# dp_tape_cutting_robot-logic.net
KiCad netlist of a schematic drawn in EAGLE
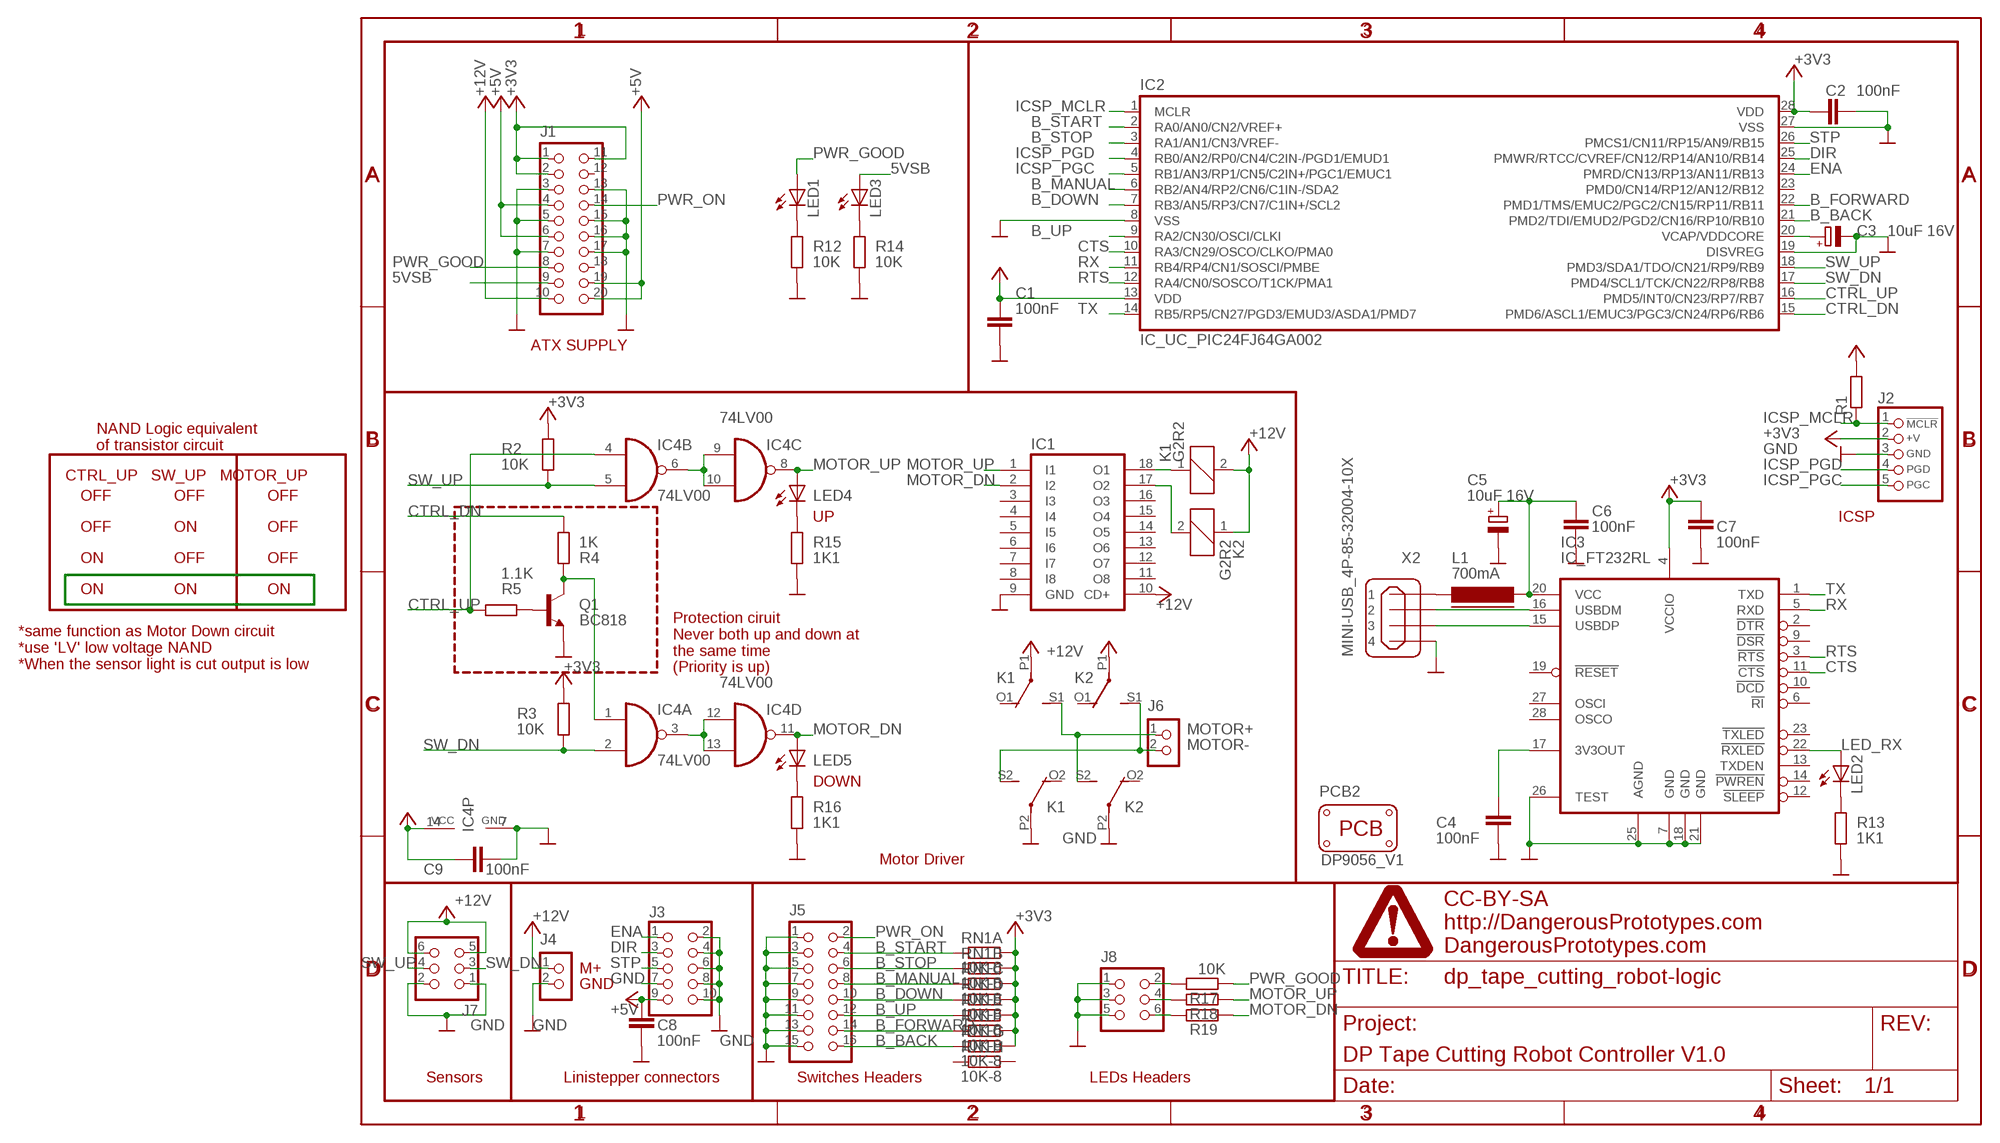
[diagram p0: schematic, sheet 1]

(export (version "E")
  (design (tool "Eeschema 10.0.6"))
  (components
    (comp (ref "C1")
      (value "100nF")
      (footprint "eagle-import:C603")
      (libsource (lib "eagle-import") (part "CAPACITOR_NPOL-0603"))
    )
    (comp (ref "C2")
      (value "100nF")
      (footprint "eagle-import:C603")
      (libsource (lib "eagle-import") (part "CAPACITOR_NPOL-0603"))
    )
    (comp (ref "C3")
      (value "10uF 16V")
      (footprint "eagle-import:SMC_A")
      (libsource (lib "eagle-import") (part "CAPACITOR_POL-SMC_A"))
    )
    (comp (ref "C4")
      (value "100nF")
      (footprint "eagle-import:C603")
      (libsource (lib "eagle-import") (part "CAPACITOR_NPOL-0603"))
    )
    (comp (ref "C5")
      (value "10uF 16V")
      (footprint "eagle-import:SMC_A")
      (libsource (lib "eagle-import") (part "CAPACITOR_POL-SMC_A"))
    )
    (comp (ref "C6")
      (value "100nF")
      (footprint "eagle-import:C603")
      (libsource (lib "eagle-import") (part "CAPACITOR_NPOL-0603"))
    )
    (comp (ref "C7")
      (value "100nF")
      (footprint "eagle-import:C603")
      (libsource (lib "eagle-import") (part "CAPACITOR_NPOL-0603"))
    )
    (comp (ref "C8")
      (value "100nF")
      (footprint "eagle-import:C603")
      (libsource (lib "eagle-import") (part "CAPACITOR_NPOL-0603"))
    )
    (comp (ref "C9")
      (value "100nF")
      (footprint "eagle-import:C603")
      (libsource (lib "eagle-import") (part "CAPACITOR_NPOL-0603"))
    )
    (comp (ref "IC1")
      (value "IC_ULN2803AN")
      (footprint "eagle-import:DIL18")
      (libsource (lib "eagle-import") (part "IC_ULN2803AN"))
    )
    (comp (ref "IC2")
      (value "IC_UC_PIC24FJ64GA002")
      (footprint "eagle-import:SSOP-28")
      (libsource (lib "eagle-import") (part "IC_UC_PIC24FJ64GA002"))
    )
    (comp (ref "IC3")
      (value "IC_FT232RL")
      (footprint "eagle-import:SSOP-28")
      (libsource (lib "eagle-import") (part "IC_FT232RL"))
    )
    (comp (ref "IC4")
      (value "74LV00")
      (footprint "eagle-import:SO14")
      (libsource (lib "eagle-import") (part "7400DAC"))
    )
    (comp (ref "J1")
      (value "CON_ATX_PWR-90DEG")
      (footprint "eagle-import:CON_ATX_PWR_90DEG")
      (libsource (lib "eagle-import") (part "CON_ATX_PWR-90DEG"))
    )
    (comp (ref "J2")
      (value "CON_HEADER_PRG_PIC_ICSP0.1INCH_A")
      (footprint "eagle-import:HEADER_PRG_1X05")
      (libsource (lib "eagle-import") (part "CON_HEADER_PRG_PIC_ICSP0.1INCH_A"))
    )
    (comp (ref "J3")
      (value "CON_HEADER_2X05-PTH")
      (footprint "eagle-import:M2X5")
      (libsource (lib "eagle-import") (part "CON_HEADER_2X05-PTH"))
    )
    (comp (ref "J4")
      (value "CON_TERMINAL_BLOCK_02-5MM")
      (footprint "eagle-import:TERMINAL_BLOCK_2P_5")
      (libsource (lib "eagle-import") (part "CON_TERMINAL_BLOCK_02-5MM"))
    )
    (comp (ref "J5")
      (value "CON_HEADER_2X08")
      (footprint "eagle-import:M2X8")
      (libsource (lib "eagle-import") (part "CON_HEADER_2X08"))
    )
    (comp (ref "J6")
      (value "CON_TERMINAL_BLOCK_02-5MM")
      (footprint "eagle-import:TERMINAL_BLOCK_2P_5")
      (libsource (lib "eagle-import") (part "CON_TERMINAL_BLOCK_02-5MM"))
    )
    (comp (ref "J7")
      (value "CON_HEADER_2X03-PTH")
      (footprint "eagle-import:M2X3")
      (libsource (lib "eagle-import") (part "CON_HEADER_2X03-PTH"))
    )
    (comp (ref "J8")
      (value "CON_HEADER_2X03-PTH")
      (footprint "eagle-import:M2X3")
      (libsource (lib "eagle-import") (part "CON_HEADER_2X03-PTH"))
    )
    (comp (ref "K1")
      (value "G2R2")
      (footprint "eagle-import:G2R2")
      (fields (field (name "MF") "OMRON COMPONENTS USA") (field (name "MPN") "G2R-2-DC6"))
      (libsource (lib "eagle-import") (part "G2R2"))
    )
    (comp (ref "K2")
      (value "G2R2")
      (footprint "eagle-import:G2R2")
      (fields
        (field (name "MF") "OMRON COMPONENTS USA")
        (field (name "MPN") "G2R-2-DC6")
        (field (name "MF_1") "OMRON COMPONENTS USA")
        (field (name "MPN_1") "G2R-2-DC6")
        (field (name "OC_FARNELL") "unknown")
        (field (name "OC_NEWARK") "89C5317")
      )
      (libsource (lib "eagle-import") (part "G2R2"))
    )
    (comp (ref "L1")
      (value "700mA")
      (footprint "eagle-import:FB805")
      (libsource (lib "eagle-import") (part "FERRITE-0805"))
    )
    (comp (ref "LED1")
      (value "LED-0805")
      (footprint "eagle-import:LED-805")
      (libsource (lib "eagle-import") (part "LED-0805"))
    )
    (comp (ref "LED2")
      (value "LED-0805")
      (footprint "eagle-import:LED-805")
      (libsource (lib "eagle-import") (part "LED-0805"))
    )
    (comp (ref "LED3")
      (value "LED-0805")
      (footprint "eagle-import:LED-805")
      (libsource (lib "eagle-import") (part "LED-0805"))
    )
    (comp (ref "LED4")
      (value "LED-0805")
      (footprint "eagle-import:LED-805")
      (libsource (lib "eagle-import") (part "LED-0805"))
    )
    (comp (ref "LED5")
      (value "LED-0805")
      (footprint "eagle-import:LED-805")
      (libsource (lib "eagle-import") (part "LED-0805"))
    )
    (comp (ref "PCB2")
      (value "PCB_DP_RECTANGLE-56X90")
      (footprint "eagle-import:DP9056_V1")
      (libsource (lib "eagle-import") (part "PCB_DP_RECTANGLE-56X90"))
    )
    (comp (ref "Q1")
      (value "BC818")
      (footprint "eagle-import:SOT-23")
      (libsource (lib "eagle-import") (part "TRANSISTOR_BJT_NPN-SOT-23-BEC"))
    )
    (comp (ref "R1")
      (value "RESISTOR-0603")
      (footprint "eagle-import:R603")
      (libsource (lib "eagle-import") (part "RESISTOR-0603"))
    )
    (comp (ref "R2")
      (value "10K")
      (footprint "eagle-import:R603")
      (libsource (lib "eagle-import") (part "RESISTOR-0603"))
    )
    (comp (ref "R3")
      (value "10K")
      (footprint "eagle-import:R603")
      (libsource (lib "eagle-import") (part "RESISTOR-0603"))
    )
    (comp (ref "R4")
      (value "1K")
      (footprint "eagle-import:R603")
      (libsource (lib "eagle-import") (part "RESISTOR-0603"))
    )
    (comp (ref "R5")
      (value "1.1K")
      (footprint "eagle-import:R603")
      (libsource (lib "eagle-import") (part "RESISTOR-0603"))
    )
    (comp (ref "R12")
      (value "10K")
      (footprint "eagle-import:R603")
      (libsource (lib "eagle-import") (part "RESISTOR-0603"))
    )
    (comp (ref "R13")
      (value "1K1")
      (footprint "eagle-import:R603")
      (libsource (lib "eagle-import") (part "RESISTOR-0603"))
    )
    (comp (ref "R14")
      (value "10K")
      (footprint "eagle-import:R603")
      (libsource (lib "eagle-import") (part "RESISTOR-0603"))
    )
    (comp (ref "R15")
      (value "1K1")
      (footprint "eagle-import:R603")
      (libsource (lib "eagle-import") (part "RESISTOR-0603"))
    )
    (comp (ref "R16")
      (value "1K1")
      (footprint "eagle-import:R603")
      (libsource (lib "eagle-import") (part "RESISTOR-0603"))
    )
    (comp (ref "R17")
      (value "10K")
      (footprint "eagle-import:R603")
      (libsource (lib "eagle-import") (part "RESISTOR-0603"))
    )
    (comp (ref "R18")
      (value "RESISTOR-0603")
      (footprint "eagle-import:R603")
      (libsource (lib "eagle-import") (part "RESISTOR-0603"))
    )
    (comp (ref "R19")
      (value "RESISTOR-0603")
      (footprint "eagle-import:R603")
      (libsource (lib "eagle-import") (part "RESISTOR-0603"))
    )
    (comp (ref "RN1")
      (value "10K-8")
      (footprint "eagle-import:CAT16-F8_CAT16-J8")
      (libsource (lib "eagle-import") (part "RESISTOR_ARRAY_8"))
    )
    (comp (ref "U$1")
      (value "FRAME_DINA4_L")
      (footprint "eagle-import:DP_LOGO")
      (fields
        (field (name "PROJECT") "DP Tape Cutting Robot Controller V1.0")
        (field (name "URL1") "http://DangerousPrototypes.com")
      )
      (libsource (lib "eagle-import") (part "FRAME_DINA4_L"))
    )
    (comp (ref "X2")
      (value "MINI-USB_4P-85-32004-10X")
      (footprint "eagle-import:85-32004-10X")
      (libsource (lib "eagle-import") (part "MINI-USB_4P-85-32004-10X"))
    )
  )
  (nets
    (net (code "1") (name "/5VSB") (class "Default")
      (node (ref "J1") (pin "9") (pinfunction "17_9") (pintype "passive"))
      (node (ref "LED3") (pin "A") (pinfunction "A_A") (pintype "passive"))
    )
    (net (code "2") (name "/B_BACK") (class "Default")
      (node (ref "IC2") (pin "21") (pinfunction "PMD2/TDI/EMUD2/PGD2/CN16/RP10/RB10_21") (pintype "bidirectional"))
      (node (ref "J5") (pin "16") (pinfunction "16_16") (pintype "passive"))
      (node (ref "RN1") (pin "7") (pinfunction "1_7") (pintype "passive"))
    )
    (net (code "3") (name "/B_DOWN") (class "Default")
      (node (ref "IC2") (pin "7") (pinfunction "RB3/AN5/RP3/CN7/C1IN+/SCL2_7") (pintype "bidirectional"))
      (node (ref "J5") (pin "10") (pinfunction "10_10") (pintype "passive"))
      (node (ref "RN1") (pin "4") (pinfunction "1_4") (pintype "passive"))
    )
    (net (code "4") (name "/B_FORWARD") (class "Default")
      (node (ref "IC2") (pin "22") (pinfunction "PMD1/TMS/EMUC2/PGC2/CN15/RP11/RB11_22") (pintype "bidirectional"))
      (node (ref "J5") (pin "14") (pinfunction "14_14") (pintype "passive"))
      (node (ref "RN1") (pin "6") (pinfunction "1_6") (pintype "passive"))
    )
    (net (code "5") (name "/B_MANUAL") (class "Default")
      (node (ref "IC2") (pin "6") (pinfunction "RB2/AN4/RP2/CN6/C1IN-/SDA2_6") (pintype "bidirectional"))
      (node (ref "J5") (pin "8") (pinfunction "8_8") (pintype "passive"))
      (node (ref "RN1") (pin "3") (pinfunction "1_3") (pintype "passive"))
    )
    (net (code "6") (name "/B_START") (class "Default")
      (node (ref "IC2") (pin "2") (pinfunction "RA0/AN0/CN2/VREF+_2") (pintype "bidirectional"))
      (node (ref "J5") (pin "4") (pinfunction "4_4") (pintype "passive"))
      (node (ref "RN1") (pin "1") (pinfunction "1_1") (pintype "passive"))
    )
    (net (code "7") (name "/B_STOP") (class "Default")
      (node (ref "IC2") (pin "3") (pinfunction "RA1/AN1/CN3/VREF-_3") (pintype "bidirectional"))
      (node (ref "J5") (pin "6") (pinfunction "6_6") (pintype "passive"))
      (node (ref "RN1") (pin "2") (pinfunction "1_2") (pintype "passive"))
    )
    (net (code "8") (name "/B_UP") (class "Default")
      (node (ref "IC2") (pin "9") (pinfunction "RA2/CN30/OSCI/CLKI_9") (pintype "bidirectional"))
      (node (ref "J5") (pin "12") (pinfunction "12_12") (pintype "passive"))
      (node (ref "RN1") (pin "5") (pinfunction "1_5") (pintype "passive"))
    )
    (net (code "9") (name "/CTRL_DN") (class "Default")
      (node (ref "IC2") (pin "15") (pinfunction "PMD6/ASCL1/EMUC3/PGC3/CN24/RP6/RB6_15") (pintype "bidirectional"))
      (node (ref "R4") (pin "1") (pinfunction "1_1") (pintype "passive"))
    )
    (net (code "10") (name "/CTRL_UP") (class "Default")
      (node (ref "IC2") (pin "16") (pinfunction "PMD5/INT0/CN23/RP7/RB7_16") (pintype "bidirectional"))
      (node (ref "IC4") (pin "4") (pinfunction "I0_4") (pintype "input"))
      (node (ref "R5") (pin "1") (pinfunction "1_1") (pintype "passive"))
    )
    (net (code "11") (name "/CTS") (class "Default")
      (node (ref "IC2") (pin "10") (pinfunction "RA3/CN29/OSCO/CLKO/PMA0_10") (pintype "bidirectional"))
      (node (ref "IC3") (pin "11") (pinfunction "~{CTS}_11") (pintype "bidirectional"))
    )
    (net (code "12") (name "/DIR") (class "Default")
      (node (ref "IC2") (pin "25") (pinfunction "PMWR/RTCC/CVREF/CN12/RP14/AN10/RB14_25") (pintype "bidirectional"))
      (node (ref "J3") (pin "3") (pinfunction "3_3") (pintype "passive"))
    )
    (net (code "13") (name "/ENA") (class "Default")
      (node (ref "IC2") (pin "24") (pinfunction "PMRD/CN13/RP13/AN11/RB13_24") (pintype "bidirectional"))
      (node (ref "J3") (pin "1") (pinfunction "1_1") (pintype "passive"))
    )
    (net (code "14") (name "/ICSP_MCLR") (class "Default")
      (node (ref "IC2") (pin "1") (pinfunction "MCLR_1") (pintype "input"))
      (node (ref "J2") (pin "1") (pinfunction "/MCLR_1") (pintype "passive"))
      (node (ref "R1") (pin "1") (pinfunction "1_1") (pintype "passive"))
    )
    (net (code "15") (name "/ICSP_PGC") (class "Default")
      (node (ref "IC2") (pin "5") (pinfunction "RB1/AN3/RP1/CN5/C2IN+/PGC1/EMUC1_5") (pintype "bidirectional"))
      (node (ref "J2") (pin "5") (pinfunction "PGC_5") (pintype "passive"))
    )
    (net (code "16") (name "/ICSP_PGD") (class "Default")
      (node (ref "IC2") (pin "4") (pinfunction "RB0/AN2/RP0/CN4/C2IN-/PGD1/EMUD1_4") (pintype "bidirectional"))
      (node (ref "J2") (pin "4") (pinfunction "PGD_4") (pintype "passive"))
    )
    (net (code "17") (name "/LED_RX") (class "Default")
      (node (ref "IC3") (pin "22") (pinfunction "~{RXLED}_22") (pintype "bidirectional"))
      (node (ref "LED2") (pin "A") (pinfunction "A_A") (pintype "passive"))
    )
    (net (code "18") (name "/MOTOR+") (class "Default")
      (node (ref "J6") (pin "1") (pinfunction "1_1") (pintype "passive"))
      (node (ref "K1") (pin "S1") (pinfunction "S_S1") (pintype "passive"))
      (node (ref "K2") (pin "S2") (pinfunction "S_S2") (pintype "passive"))
    )
    (net (code "19") (name "/MOTOR-") (class "Default")
      (node (ref "J6") (pin "2") (pinfunction "2_2") (pintype "passive"))
      (node (ref "K1") (pin "S2") (pinfunction "S_S2") (pintype "passive"))
      (node (ref "K2") (pin "S1") (pinfunction "S_S1") (pintype "passive"))
    )
    (net (code "20") (name "/MOTOR_DN") (class "Default")
      (node (ref "IC1") (pin "2") (pinfunction "I2_2") (pintype "input"))
      (node (ref "IC4") (pin "11") (pinfunction "O_11") (pintype "output"))
      (node (ref "LED5") (pin "A") (pinfunction "A_A") (pintype "passive"))
      (node (ref "R19") (pin "1") (pinfunction "1_1") (pintype "passive"))
    )
    (net (code "21") (name "/MOTOR_UP") (class "Default")
      (node (ref "IC1") (pin "1") (pinfunction "I1_1") (pintype "input"))
      (node (ref "IC4") (pin "8") (pinfunction "O_8") (pintype "output"))
      (node (ref "LED4") (pin "A") (pinfunction "A_A") (pintype "passive"))
      (node (ref "R18") (pin "1") (pinfunction "1_1") (pintype "passive"))
    )
    (net (code "22") (name "/PWR_GOOD") (class "Default")
      (node (ref "J1") (pin "8") (pinfunction "15_8") (pintype "passive"))
      (node (ref "LED1") (pin "A") (pinfunction "A_A") (pintype "passive"))
      (node (ref "R17") (pin "1") (pinfunction "1_1") (pintype "passive"))
    )
    (net (code "23") (name "/PWR_ON") (class "Default")
      (node (ref "J1") (pin "14") (pinfunction "8_14") (pintype "passive"))
      (node (ref "J5") (pin "2") (pinfunction "2_2") (pintype "passive"))
    )
    (net (code "24") (name "/RTS") (class "Default")
      (node (ref "IC2") (pin "12") (pinfunction "RA4/CN0/SOSCO/T1CK/PMA1_12") (pintype "bidirectional"))
      (node (ref "IC3") (pin "3") (pinfunction "~{RTS}_3") (pintype "bidirectional"))
    )
    (net (code "25") (name "/RX") (class "Default")
      (node (ref "IC2") (pin "11") (pinfunction "RB4/RP4/CN1/SOSCI/PMBE_11") (pintype "bidirectional"))
      (node (ref "IC3") (pin "5") (pinfunction "RXD_5") (pintype "bidirectional"))
    )
    (net (code "26") (name "/STP") (class "Default")
      (node (ref "IC2") (pin "26") (pinfunction "PMCS1/CN11/RP15/AN9/RB15_26") (pintype "bidirectional"))
      (node (ref "J3") (pin "5") (pinfunction "5_5") (pintype "passive"))
    )
    (net (code "27") (name "/SW_DN") (class "Default")
      (node (ref "IC2") (pin "17") (pinfunction "PMD4/SCL1/TCK/CN22/RP8/RB8_17") (pintype "bidirectional"))
      (node (ref "IC4") (pin "2") (pinfunction "I1_2") (pintype "input"))
      (node (ref "J7") (pin "3") (pinfunction "3_3") (pintype "passive"))
      (node (ref "R3") (pin "1") (pinfunction "1_1") (pintype "passive"))
    )
    (net (code "28") (name "/SW_UP") (class "Default")
      (node (ref "IC2") (pin "18") (pinfunction "PMD3/SDA1/TDO/CN21/RP9/RB9_18") (pintype "bidirectional"))
      (node (ref "IC4") (pin "5") (pinfunction "I1_5") (pintype "input"))
      (node (ref "J7") (pin "4") (pinfunction "4_4") (pintype "passive"))
      (node (ref "R2") (pin "1") (pinfunction "1_1") (pintype "passive"))
    )
    (net (code "29") (name "/TX") (class "Default")
      (node (ref "IC2") (pin "14") (pinfunction "RB5/RP5/CN27/PGD3/EMUD3/ASDA1/PMD7_14") (pintype "bidirectional"))
      (node (ref "IC3") (pin "1") (pinfunction "TXD_1") (pintype "bidirectional"))
    )
    (net (code "30") (name "Net-(IC1-O1)") (class "Default")
      (node (ref "IC1") (pin "18") (pinfunction "O1_18") (pintype "open_collector"))
      (node (ref "K1") (pin "1") (pinfunction "1_1") (pintype "passive"))
    )
    (net (code "31") (name "Net-(IC1-O2)") (class "Default")
      (node (ref "IC1") (pin "17") (pinfunction "O2_17") (pintype "open_collector"))
      (node (ref "K2") (pin "2") (pinfunction "2_2") (pintype "passive"))
    )
    (net (code "32") (name "Net-(IC2-VCAP{slash}VDDCORE)") (class "Default")
      (node (ref "C3") (pin "+") (pinfunction "+_+") (pintype "passive"))
      (node (ref "IC2") (pin "20") (pinfunction "VCAP/VDDCORE_20") (pintype "power_in"))
    )
    (net (code "33") (name "Net-(IC3-3V3OUT)") (class "Default")
      (node (ref "C4") (pin "2") (pinfunction "2_2") (pintype "passive"))
      (node (ref "IC3") (pin "17") (pinfunction "3V3OUT_17") (pintype "bidirectional"))
    )
    (net (code "34") (name "Net-(IC3-USBDM)") (class "Default")
      (node (ref "IC3") (pin "16") (pinfunction "USBDM_16") (pintype "bidirectional"))
      (node (ref "X2") (pin "2") (pinfunction "2_2") (pintype "passive"))
    )
    (net (code "35") (name "Net-(IC3-USBDP)") (class "Default")
      (node (ref "IC3") (pin "15") (pinfunction "USBDP_15") (pintype "bidirectional"))
      (node (ref "X2") (pin "3") (pinfunction "3_3") (pintype "passive"))
    )
    (net (code "36") (name "Net-(IC3-VCC)") (class "Default")
      (node (ref "C5") (pin "+") (pinfunction "+_+") (pintype "passive"))
      (node (ref "C6") (pin "2") (pinfunction "2_2") (pintype "passive"))
      (node (ref "IC3") (pin "20") (pinfunction "VCC_20") (pintype "bidirectional"))
      (node (ref "L1") (pin "2") (pinfunction "2_2") (pintype "passive"))
    )
    (net (code "37") (name "Net-(IC4A-I0)") (class "Default")
      (node (ref "IC4") (pin "1") (pinfunction "I0_1") (pintype "input"))
      (node (ref "Q1") (pin "3") (pinfunction "C_3") (pintype "passive"))
      (node (ref "R4") (pin "2") (pinfunction "2_2") (pintype "passive"))
    )
    (net (code "38") (name "Net-(IC4A-O)") (class "Default")
      (node (ref "IC4") (pin "12") (pinfunction "I0_12") (pintype "input"))
      (node (ref "IC4") (pin "13") (pinfunction "I1_13") (pintype "input"))
      (node (ref "IC4") (pin "3") (pinfunction "O_3") (pintype "output"))
    )
    (net (code "39") (name "Net-(IC4B-O)") (class "Default")
      (node (ref "IC4") (pin "10") (pinfunction "I1_10") (pintype "input"))
      (node (ref "IC4") (pin "6") (pinfunction "O_6") (pintype "output"))
      (node (ref "IC4") (pin "9") (pinfunction "I0_9") (pintype "input"))
    )
    (net (code "40") (name "Net-(J8-Pad2)") (class "Default")
      (node (ref "J8") (pin "2") (pinfunction "2_2") (pintype "passive"))
      (node (ref "R17") (pin "2") (pinfunction "2_2") (pintype "passive"))
    )
    (net (code "41") (name "Net-(J8-Pad4)") (class "Default")
      (node (ref "J8") (pin "4") (pinfunction "4_4") (pintype "passive"))
      (node (ref "R18") (pin "2") (pinfunction "2_2") (pintype "passive"))
    )
    (net (code "42") (name "Net-(J8-Pad6)") (class "Default")
      (node (ref "J8") (pin "6") (pinfunction "6_6") (pintype "passive"))
      (node (ref "R19") (pin "2") (pinfunction "2_2") (pintype "passive"))
    )
    (net (code "43") (name "Net-(L1-Pad1)") (class "Default")
      (node (ref "L1") (pin "1") (pinfunction "1_1") (pintype "passive"))
      (node (ref "X2") (pin "1") (pinfunction "1_1") (pintype "passive"))
    )
    (net (code "44") (name "Net-(LED1-PadC)") (class "Default")
      (node (ref "LED1") (pin "C") (pinfunction "C_C") (pintype "passive"))
      (node (ref "R12") (pin "2") (pinfunction "2_2") (pintype "passive"))
    )
    (net (code "45") (name "Net-(LED2-PadC)") (class "Default")
      (node (ref "LED2") (pin "C") (pinfunction "C_C") (pintype "passive"))
      (node (ref "R13") (pin "2") (pinfunction "2_2") (pintype "passive"))
    )
    (net (code "46") (name "Net-(LED3-PadC)") (class "Default")
      (node (ref "LED3") (pin "C") (pinfunction "C_C") (pintype "passive"))
      (node (ref "R14") (pin "2") (pinfunction "2_2") (pintype "passive"))
    )
    (net (code "47") (name "Net-(LED4-PadC)") (class "Default")
      (node (ref "LED4") (pin "C") (pinfunction "C_C") (pintype "passive"))
      (node (ref "R15") (pin "2") (pinfunction "2_2") (pintype "passive"))
    )
    (net (code "48") (name "Net-(LED5-PadC)") (class "Default")
      (node (ref "LED5") (pin "C") (pinfunction "C_C") (pintype "passive"))
      (node (ref "R16") (pin "2") (pinfunction "2_2") (pintype "passive"))
    )
    (net (code "49") (name "Net-(Q1-B)") (class "Default")
      (node (ref "Q1") (pin "1") (pinfunction "B_1") (pintype "passive"))
      (node (ref "R5") (pin "2") (pinfunction "2_2") (pintype "passive"))
    )
    (net (code "50") (name "SUPPLY_+3V3") (class "Default")
      (node (ref "C1") (pin "1") (pinfunction "1_1") (pintype "passive"))
      (node (ref "C2") (pin "2") (pinfunction "2_2") (pintype "passive"))
      (node (ref "C7") (pin "2") (pinfunction "2_2") (pintype "passive"))
      (node (ref "C9") (pin "2") (pinfunction "2_2") (pintype "passive"))
      (node (ref "IC2") (pin "13") (pinfunction "VDD_13") (pintype "power_in"))
      (node (ref "IC2") (pin "28") (pinfunction "VDD_28") (pintype "power_in"))
      (node (ref "IC3") (pin "4") (pinfunction "VCCIO_4") (pintype "bidirectional"))
      (node (ref "IC4") (pin "14") (pinfunction "VCC_14") (pintype "power_in"))
      (node (ref "J1") (pin "1") (pinfunction "1_1") (pintype "passive"))
      (node (ref "J1") (pin "11") (pinfunction "2_11") (pintype "passive"))
      (node (ref "J1") (pin "2") (pinfunction "3_2") (pintype "passive"))
      (node (ref "J2") (pin "2") (pinfunction "+V_2") (pintype "passive"))
      (node (ref "R1") (pin "2") (pinfunction "2_2") (pintype "passive"))
      (node (ref "R2") (pin "2") (pinfunction "2_2") (pintype "passive"))
      (node (ref "R3") (pin "2") (pinfunction "2_2") (pintype "passive"))
      (node (ref "RN1") (pin "10") (pinfunction "2_10") (pintype "passive"))
      (node (ref "RN1") (pin "11") (pinfunction "2_11") (pintype "passive"))
      (node (ref "RN1") (pin "12") (pinfunction "2_12") (pintype "passive"))
      (node (ref "RN1") (pin "13") (pinfunction "2_13") (pintype "passive"))
      (node (ref "RN1") (pin "14") (pinfunction "2_14") (pintype "passive"))
      (node (ref "RN1") (pin "15") (pinfunction "2_15") (pintype "passive"))
      (node (ref "RN1") (pin "16") (pinfunction "2_16") (pintype "passive"))
    )
    (net (code "51") (name "SUPPLY_+5V") (class "Default")
      (node (ref "C8") (pin "2") (pinfunction "2_2") (pintype "passive"))
      (node (ref "J1") (pin "19") (pinfunction "18_19") (pintype "passive"))
      (node (ref "J1") (pin "20") (pinfunction "20_20") (pintype "passive"))
      (node (ref "J1") (pin "4") (pinfunction "7_4") (pintype "passive"))
      (node (ref "J1") (pin "6") (pinfunction "11_6") (pintype "passive"))
      (node (ref "J3") (pin "9") (pinfunction "9_9") (pintype "passive"))
    )
    (net (code "52") (name "SUPPLY_+12V") (class "Default")
      (node (ref "IC1") (pin "10") (pinfunction "CD+_10") (pintype "passive"))
      (node (ref "J1") (pin "10") (pinfunction "19_10") (pintype "passive"))
      (node (ref "J4") (pin "1") (pinfunction "1_1") (pintype "passive"))
      (node (ref "J7") (pin "5") (pinfunction "5_5") (pintype "passive"))
      (node (ref "J7") (pin "6") (pinfunction "6_6") (pintype "passive"))
      (node (ref "K1") (pin "2") (pinfunction "2_2") (pintype "passive"))
      (node (ref "K1") (pin "P1") (pinfunction "P_P1") (pintype "passive"))
      (node (ref "K2") (pin "1") (pinfunction "1_1") (pintype "passive"))
      (node (ref "K2") (pin "P1") (pinfunction "P_P1") (pintype "passive"))
    )
    (net (code "53") (name "SUPPLY_GND") (class "Default")
      (node (ref "C1") (pin "2") (pinfunction "2_2") (pintype "passive"))
      (node (ref "C2") (pin "1") (pinfunction "1_1") (pintype "passive"))
      (node (ref "C3") (pin "-") (pinfunction "-_-") (pintype "passive"))
      (node (ref "C4") (pin "1") (pinfunction "1_1") (pintype "passive"))
      (node (ref "C5") (pin "-") (pinfunction "-_-") (pintype "passive"))
      (node (ref "C6") (pin "1") (pinfunction "1_1") (pintype "passive"))
      (node (ref "C7") (pin "1") (pinfunction "1_1") (pintype "passive"))
      (node (ref "C8") (pin "1") (pinfunction "1_1") (pintype "passive"))
      (node (ref "C9") (pin "1") (pinfunction "1_1") (pintype "passive"))
      (node (ref "IC1") (pin "9") (pinfunction "GND_9") (pintype "power_in"))
      (node (ref "IC2") (pin "19") (pinfunction "DISVREG_19") (pintype "power_in"))
      (node (ref "IC2") (pin "27") (pinfunction "VSS_27") (pintype "power_in"))
      (node (ref "IC2") (pin "8") (pinfunction "VSS_8") (pintype "power_in"))
      (node (ref "IC3") (pin "18") (pinfunction "GND_18") (pintype "bidirectional"))
      (node (ref "IC3") (pin "21") (pinfunction "GND_21") (pintype "bidirectional"))
      (node (ref "IC3") (pin "25") (pinfunction "AGND_25") (pintype "bidirectional"))
      (node (ref "IC3") (pin "26") (pinfunction "TEST_26") (pintype "bidirectional"))
      (node (ref "IC3") (pin "7") (pinfunction "GND_7") (pintype "bidirectional"))
      (node (ref "IC4") (pin "7") (pinfunction "GND_7") (pintype "power_in"))
      (node (ref "J1") (pin "13") (pinfunction "6_13") (pintype "passive"))
      (node (ref "J1") (pin "15") (pinfunction "10_15") (pintype "passive"))
      (node (ref "J1") (pin "16") (pinfunction "12_16") (pintype "passive"))
      (node (ref "J1") (pin "17") (pinfunction "14_17") (pintype "passive"))
      (node (ref "J1") (pin "3") (pinfunction "5_3") (pintype "passive"))
      (node (ref "J1") (pin "5") (pinfunction "9_5") (pintype "passive"))
      (node (ref "J1") (pin "7") (pinfunction "13_7") (pintype "passive"))
      (node (ref "J2") (pin "3") (pinfunction "GND_3") (pintype "passive"))
      (node (ref "J3") (pin "10") (pinfunction "10_10") (pintype "passive"))
      (node (ref "J3") (pin "2") (pinfunction "2_2") (pintype "passive"))
      (node (ref "J3") (pin "4") (pinfunction "4_4") (pintype "passive"))
      (node (ref "J3") (pin "6") (pinfunction "6_6") (pintype "passive"))
      (node (ref "J3") (pin "7") (pinfunction "7_7") (pintype "passive"))
      (node (ref "J3") (pin "8") (pinfunction "8_8") (pintype "passive"))
      (node (ref "J4") (pin "2") (pinfunction "2_2") (pintype "passive"))
      (node (ref "J5") (pin "1") (pinfunction "1_1") (pintype "passive"))
      (node (ref "J5") (pin "11") (pinfunction "11_11") (pintype "passive"))
      (node (ref "J5") (pin "13") (pinfunction "13_13") (pintype "passive"))
      (node (ref "J5") (pin "15") (pinfunction "15_15") (pintype "passive"))
      (node (ref "J5") (pin "3") (pinfunction "3_3") (pintype "passive"))
      (node (ref "J5") (pin "5") (pinfunction "5_5") (pintype "passive"))
      (node (ref "J5") (pin "7") (pinfunction "7_7") (pintype "passive"))
      (node (ref "J5") (pin "9") (pinfunction "9_9") (pintype "passive"))
      (node (ref "J7") (pin "1") (pinfunction "1_1") (pintype "passive"))
      (node (ref "J7") (pin "2") (pinfunction "2_2") (pintype "passive"))
      (node (ref "J8") (pin "1") (pinfunction "1_1") (pintype "passive"))
      (node (ref "J8") (pin "3") (pinfunction "3_3") (pintype "passive"))
      (node (ref "J8") (pin "5") (pinfunction "5_5") (pintype "passive"))
      (node (ref "K1") (pin "P2") (pinfunction "P_P2") (pintype "passive"))
      (node (ref "K2") (pin "P2") (pinfunction "P_P2") (pintype "passive"))
      (node (ref "Q1") (pin "2") (pinfunction "E_2") (pintype "passive"))
      (node (ref "R12") (pin "1") (pinfunction "1_1") (pintype "passive"))
      (node (ref "R13") (pin "1") (pinfunction "1_1") (pintype "passive"))
      (node (ref "R14") (pin "1") (pinfunction "1_1") (pintype "passive"))
      (node (ref "R15") (pin "1") (pinfunction "1_1") (pintype "passive"))
      (node (ref "R16") (pin "1") (pinfunction "1_1") (pintype "passive"))
      (node (ref "X2") (pin "4") (pinfunction "4_4") (pintype "passive"))
    )
    (net (code "54") (name "unconnected-(IC1-I3-Pad3)") (class "Default")
      (node (ref "IC1") (pin "3") (pinfunction "I3_3") (pintype "input"))
    )
    (net (code "55") (name "unconnected-(IC1-I4-Pad4)") (class "Default")
      (node (ref "IC1") (pin "4") (pinfunction "I4_4") (pintype "input"))
    )
    (net (code "56") (name "unconnected-(IC1-I5-Pad5)") (class "Default")
      (node (ref "IC1") (pin "5") (pinfunction "I5_5") (pintype "input"))
    )
    (net (code "57") (name "unconnected-(IC1-I6-Pad6)") (class "Default")
      (node (ref "IC1") (pin "6") (pinfunction "I6_6") (pintype "input"))
    )
    (net (code "58") (name "unconnected-(IC1-I7-Pad7)") (class "Default")
      (node (ref "IC1") (pin "7") (pinfunction "I7_7") (pintype "input"))
    )
    (net (code "59") (name "unconnected-(IC1-I8-Pad8)") (class "Default")
      (node (ref "IC1") (pin "8") (pinfunction "I8_8") (pintype "input"))
    )
    (net (code "60") (name "unconnected-(IC1-O3-Pad16)") (class "Default")
      (node (ref "IC1") (pin "16") (pinfunction "O3_16") (pintype "open_collector"))
    )
    (net (code "61") (name "unconnected-(IC1-O4-Pad15)") (class "Default")
      (node (ref "IC1") (pin "15") (pinfunction "O4_15") (pintype "open_collector"))
    )
    (net (code "62") (name "unconnected-(IC1-O5-Pad14)") (class "Default")
      (node (ref "IC1") (pin "14") (pinfunction "O5_14") (pintype "open_collector"))
    )
    (net (code "63") (name "unconnected-(IC1-O6-Pad13)") (class "Default")
      (node (ref "IC1") (pin "13") (pinfunction "O6_13") (pintype "open_collector"))
    )
    (net (code "64") (name "unconnected-(IC1-O7-Pad12)") (class "Default")
      (node (ref "IC1") (pin "12") (pinfunction "O7_12") (pintype "open_collector"))
    )
    (net (code "65") (name "unconnected-(IC1-O8-Pad11)") (class "Default")
      (node (ref "IC1") (pin "11") (pinfunction "O8_11") (pintype "open_collector"))
    )
    (net (code "66") (name "unconnected-(IC2-PMD0{slash}CN14{slash}RP12{slash}AN12{slash}RB12-Pad23)") (class "Default")
      (node (ref "IC2") (pin "23") (pinfunction "PMD0/CN14/RP12/AN12/RB12_23") (pintype "bidirectional"))
    )
    (net (code "67") (name "unconnected-(IC3-OSCI-Pad27)") (class "Default")
      (node (ref "IC3") (pin "27") (pinfunction "OSCI_27") (pintype "bidirectional"))
    )
    (net (code "68") (name "unconnected-(IC3-OSCO-Pad28)") (class "Default")
      (node (ref "IC3") (pin "28") (pinfunction "OSCO_28") (pintype "bidirectional"))
    )
    (net (code "69") (name "unconnected-(IC3-TXDEN-Pad13)") (class "Default")
      (node (ref "IC3") (pin "13") (pinfunction "TXDEN_13") (pintype "bidirectional"))
    )
    (net (code "70") (name "unconnected-(IC3-~{DCD}-Pad10)") (class "Default")
      (node (ref "IC3") (pin "10") (pinfunction "~{DCD}_10") (pintype "bidirectional"))
    )
    (net (code "71") (name "unconnected-(IC3-~{DSR}-Pad9)") (class "Default")
      (node (ref "IC3") (pin "9") (pinfunction "~{DSR}_9") (pintype "bidirectional"))
    )
    (net (code "72") (name "unconnected-(IC3-~{DTR}-Pad2)") (class "Default")
      (node (ref "IC3") (pin "2") (pinfunction "~{DTR}_2") (pintype "bidirectional"))
    )
    (net (code "73") (name "unconnected-(IC3-~{PWREN}-Pad14)") (class "Default")
      (node (ref "IC3") (pin "14") (pinfunction "~{PWREN}_14") (pintype "bidirectional"))
    )
    (net (code "74") (name "unconnected-(IC3-~{RESET}-Pad19)") (class "Default")
      (node (ref "IC3") (pin "19") (pinfunction "~{RESET}_19") (pintype "bidirectional"))
    )
    (net (code "75") (name "unconnected-(IC3-~{RI}-Pad6)") (class "Default")
      (node (ref "IC3") (pin "6") (pinfunction "~{RI}_6") (pintype "bidirectional"))
    )
    (net (code "76") (name "unconnected-(IC3-~{SLEEP}-Pad12)") (class "Default")
      (node (ref "IC3") (pin "12") (pinfunction "~{SLEEP}_12") (pintype "bidirectional"))
    )
    (net (code "77") (name "unconnected-(IC3-~{TXLED}-Pad23)") (class "Default")
      (node (ref "IC3") (pin "23") (pinfunction "~{TXLED}_23") (pintype "bidirectional"))
    )
    (net (code "78") (name "unconnected-(J1-4-Pad12)") (class "Default")
      (node (ref "J1") (pin "12") (pinfunction "4_12") (pintype "passive"))
    )
    (net (code "79") (name "unconnected-(J1-16-Pad18)") (class "Default")
      (node (ref "J1") (pin "18") (pinfunction "16_18") (pintype "passive"))
    )
    (net (code "80") (name "unconnected-(K1B-O-PadO1)") (class "Default")
      (node (ref "K1") (pin "O1") (pinfunction "O_O1") (pintype "passive"))
    )
    (net (code "81") (name "unconnected-(K1C-O-PadO2)") (class "Default")
      (node (ref "K1") (pin "O2") (pinfunction "O_O2") (pintype "passive"))
    )
    (net (code "82") (name "unconnected-(K2B-O-PadO1)") (class "Default")
      (node (ref "K2") (pin "O1") (pinfunction "O_O1") (pintype "passive"))
    )
    (net (code "83") (name "unconnected-(K2C-O-PadO2)") (class "Default")
      (node (ref "K2") (pin "O2") (pinfunction "O_O2") (pintype "passive"))
    )
    (net (code "84") (name "unconnected-(RN1H-1-Pad8)") (class "Default")
      (node (ref "RN1") (pin "8") (pinfunction "1_8") (pintype "passive"))
    )
    (net (code "85") (name "unconnected-(RN1H-2-Pad9)") (class "Default")
      (node (ref "RN1") (pin "9") (pinfunction "2_9") (pintype "passive"))
    )
  )
)
